# test_watch.net
KiCad netlist of a schematic drawn in Altium Designer
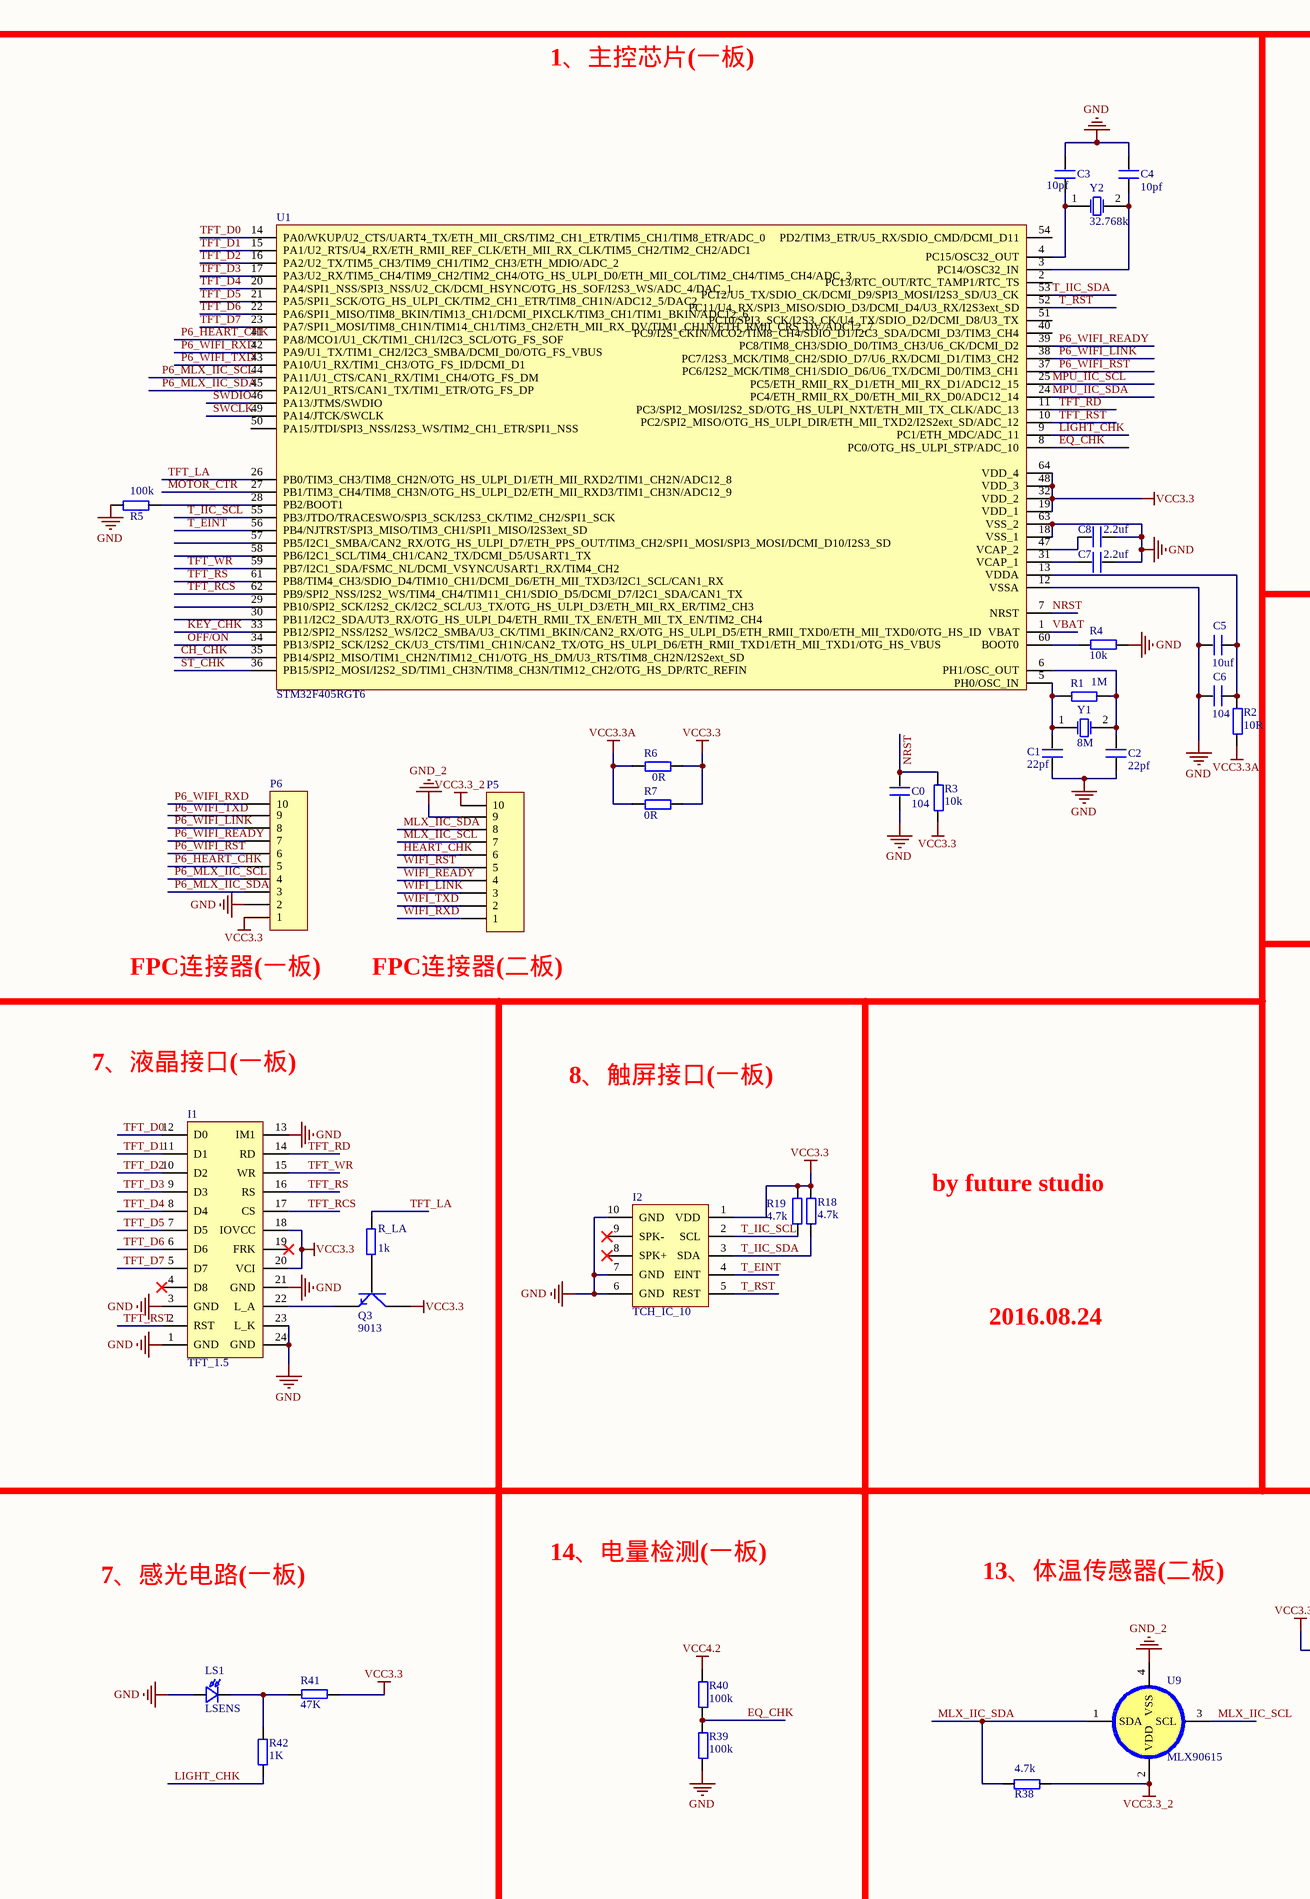
[diagram p0: test_watch.SchDoc, left]
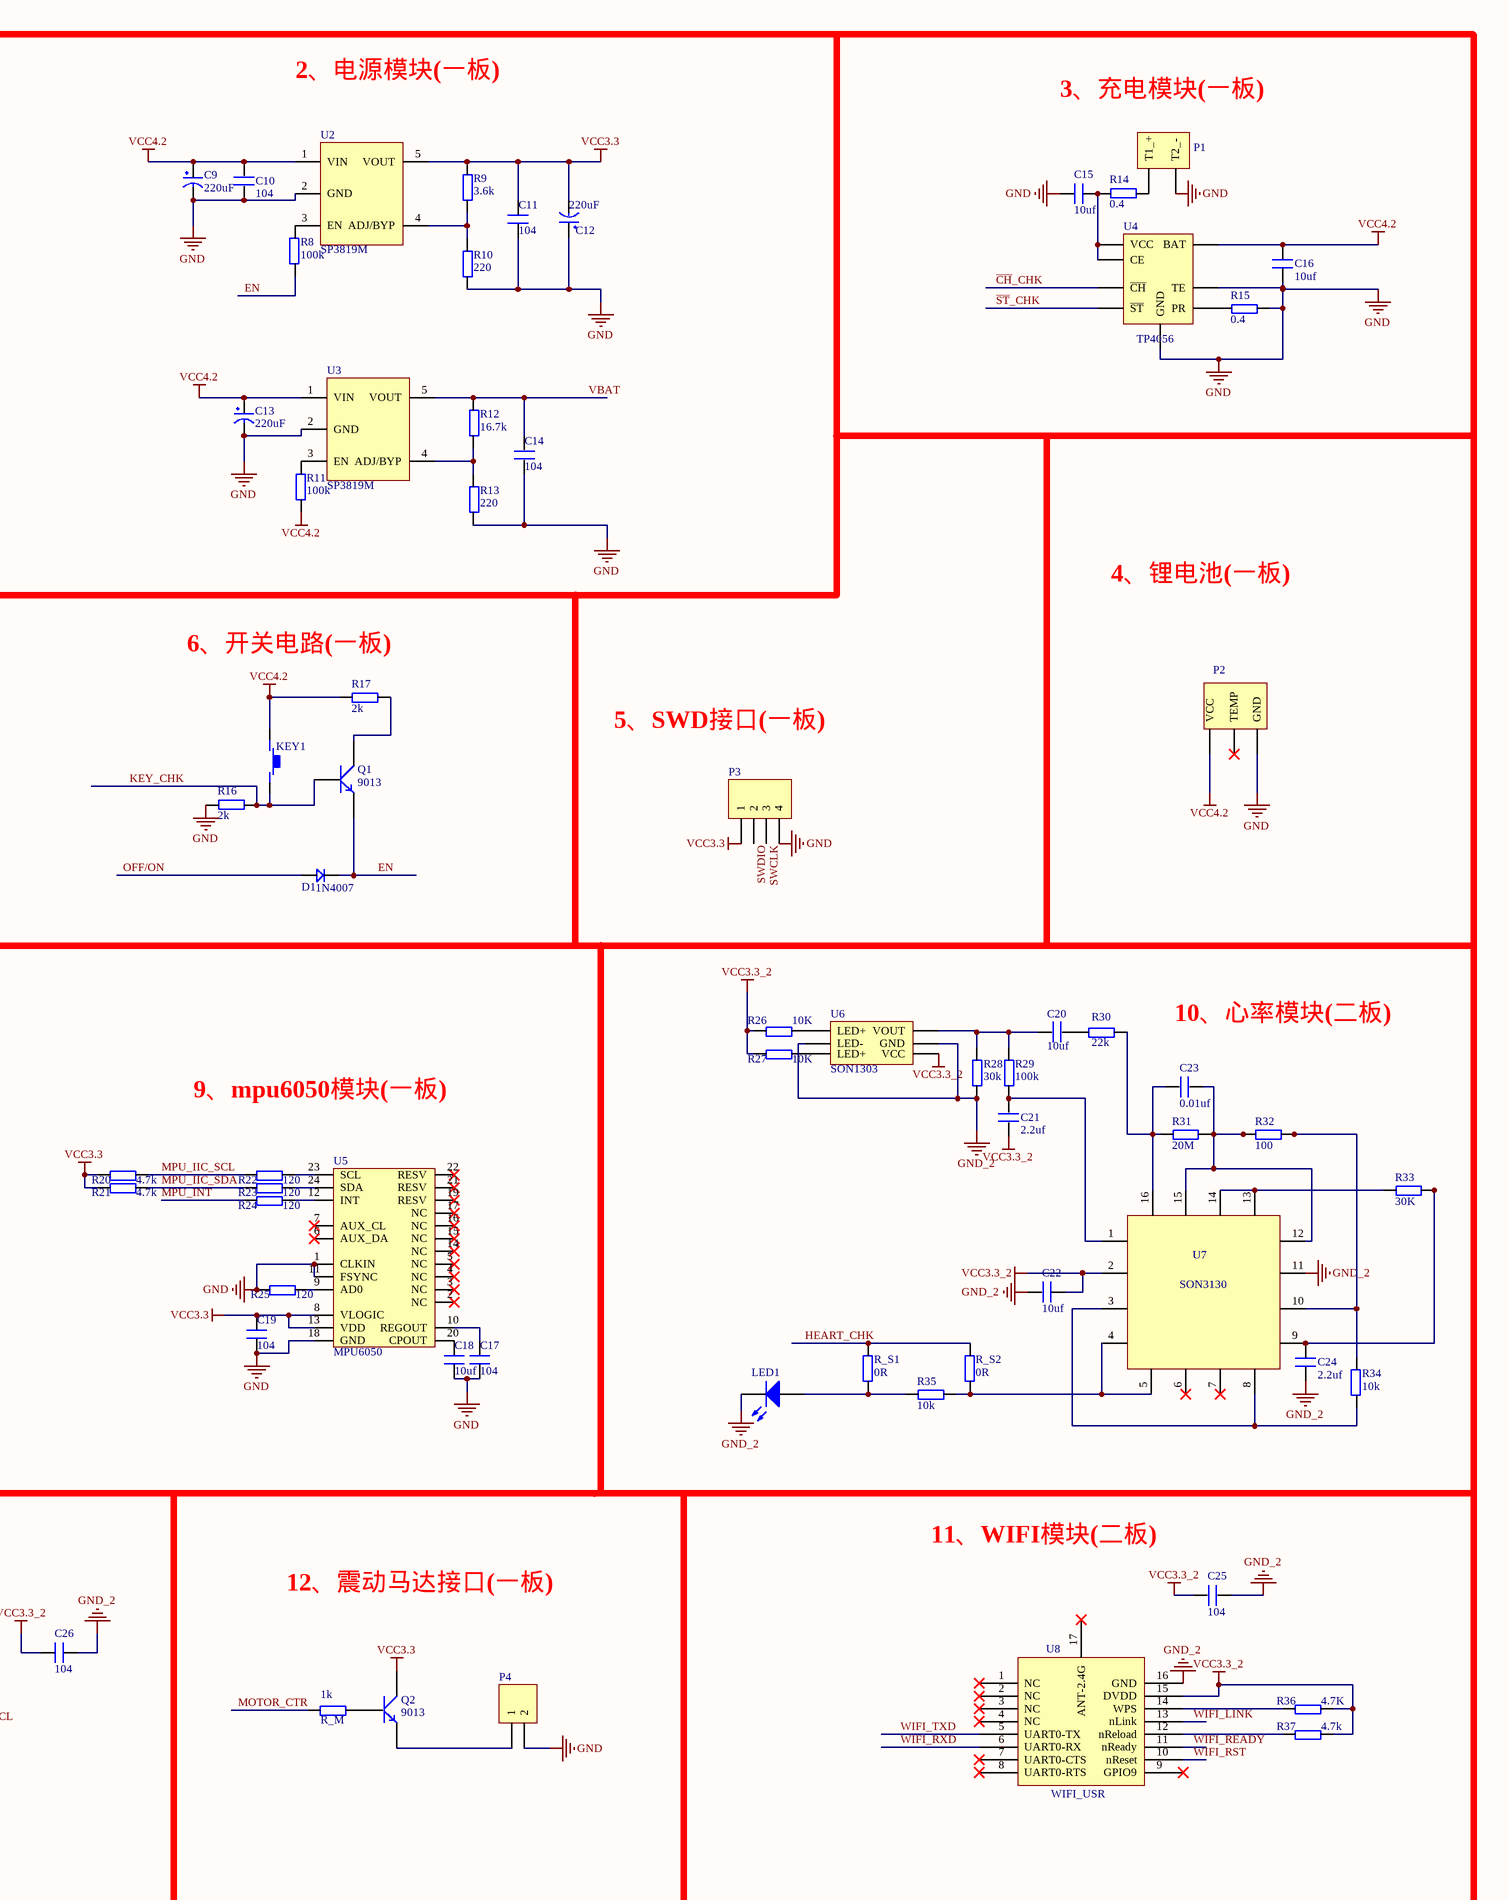
[diagram p1: test_watch.SchDoc, right]

(export (version "E")
  (design (tool "Eeschema 10.0.6"))
  (components
    (comp (ref "C0") (value "104") (footprint "C_0603") (libsource (lib "战舰STM32开发板底板封装库") (part "C")))
    (comp (ref "C1") (value "22pf") (footprint "C_0402") (libsource (lib "战舰STM32开发板底板封装库") (part "C")))
    (comp (ref "C2") (value "22pf") (footprint "C_0402") (libsource (lib "战舰STM32开发板底板封装库") (part "C")))
    (comp (ref "C3") (value "10pf") (footprint "C_0402") (libsource (lib "战舰STM32开发板底板封装库") (part "C")))
    (comp (ref "C4") (value "10pf") (footprint "C_0402") (libsource (lib "战舰STM32开发板底板封装库") (part "C")))
    (comp (ref "C5") (value "10uf") (footprint "C_0402") (libsource (lib "战舰STM32开发板底板封装库") (part "C")))
    (comp (ref "C6") (value "104") (footprint "C_0603") (libsource (lib "战舰STM32开发板底板封装库") (part "C")))
    (comp (ref "C7") (value "2.2uf") (footprint "C_0402") (libsource (lib "战舰STM32开发板底板封装库") (part "C")))
    (comp (ref "C8") (value "2.2uf") (footprint "C_0402") (libsource (lib "战舰STM32开发板底板封装库") (part "C")))
    (comp (ref "C9") (value "220uF") (footprint "C_3528") (libsource (lib "战舰STM32开发板底板封装库") (part "CAP")))
    (comp (ref "C10") (value "104") (footprint "C_0603") (libsource (lib "战舰STM32开发板底板封装库") (part "C")))
    (comp (ref "C11") (value "104") (footprint "C_0603") (libsource (lib "战舰STM32开发板底板封装库") (part "C")))
    (comp (ref "C12") (value "220uF") (footprint "C_3528") (libsource (lib "") (part "CAP_1")))
    (comp (ref "C13") (value "220uF") (footprint "C_3528") (libsource (lib "战舰STM32开发板底板封装库") (part "CAP")))
    (comp (ref "C14") (value "104") (footprint "C_0603") (libsource (lib "战舰STM32开发板底板封装库") (part "C")))
    (comp (ref "C15") (value "10uf") (footprint "C_0402") (libsource (lib "战舰STM32开发板底板封装库") (part "C")))
    (comp (ref "C16") (value "10uf") (footprint "C_0402") (libsource (lib "战舰STM32开发板底板封装库") (part "C")))
    (comp (ref "C17") (value "104") (footprint "C_0603") (libsource (lib "战舰STM32开发板底板封装库") (part "C")))
    (comp (ref "C18") (value "10uf") (footprint "C_0402") (libsource (lib "战舰STM32开发板底板封装库") (part "C")))
    (comp (ref "C19") (value "104") (footprint "C_0603") (libsource (lib "战舰STM32开发板底板封装库") (part "C")))
    (comp (ref "C20") (value "10uf") (footprint "C_0402") (libsource (lib "战舰STM32开发板底板封装库") (part "C")))
    (comp (ref "C21") (value "2.2uf") (footprint "C_0402") (libsource (lib "战舰STM32开发板底板封装库") (part "C")))
    (comp (ref "C22") (value "10uf") (footprint "C_0402") (libsource (lib "战舰STM32开发板底板封装库") (part "C")))
    (comp (ref "C23") (value "0.01uf") (footprint "C_0603") (libsource (lib "战舰STM32开发板底板封装库") (part "C")))
    (comp (ref "C24") (value "2.2uf") (footprint "C_0402") (libsource (lib "战舰STM32开发板底板封装库") (part "C")))
    (comp (ref "C25") (value "104") (footprint "C_0603") (libsource (lib "战舰STM32开发板底板封装库") (part "C")))
    (comp (ref "C26") (value "104") (footprint "C_0603") (libsource (lib "战舰STM32开发板底板封装库") (part "C")))
    (comp (ref "D1") (value "1N4007") (footprint "D_0805") (libsource (lib "战舰STM32开发板底板封装库") (part "D")))
    (comp (ref "I1")
      (value "TFT_1.5")
      (footprint "DF37NB-24DS-0.4V - duplicate")
      (libsource (lib "test_1") (part "TFT_1.5"))
    )
    (comp (ref "I2")
      (value "TCH_IC_10")
      (footprint "DF37NB-10DS-0.4V")
      (libsource (lib "test_1") (part "TCH_IC_10"))
    )
    (comp (ref "KEY1") (value "button_2pin") (footprint "SMD2_3.5") (libsource (lib "test_1") (part "KEY_2")))
    (comp (ref "LED1")
      (value "LED1")
      (footprint "D_0603")
      (description "Typical RED, GREEN, YELLOW, AMBER GaAs LED")
      (fields (field (name "PUBLISHER") "Altium Limited"))
      (libsource (lib "战舰STM32开发板底板封装库") (part "LED2"))
    )
    (comp (ref "LS1")
      (value "LSENS")
      (footprint "0805")
      (description "光敏电阻")
      (libsource (lib "test_1") (part "光敏电阻"))
    )
    (comp (ref "P1")
      (value "contactor")
      (footprint "CHARGE_2")
      (description "充电触点")
      (libsource (lib "test_1") (part "contactor"))
    )
    (comp (ref "P2")
      (value "CELL")
      (footprint "CELL_2")
      (description "锂电池")
      (libsource (lib "test_1") (part "CELL"))
    )
    (comp (ref "P3")
      (value "Header 4")
      (footprint "SWD")
      (description "Header, 4-Pin")
      (fields (field (name "PUBLISHER") "Altium Limited"))
      (libsource (lib "战舰STM32开发板底板封装库") (part "Header 4"))
    )
    (comp (ref "P4")
      (value "MIC/LINE")
      (footprint "CHARGE_2")
      (description "Header, 2-Pin")
      (fields (field (name "PUBLISHER") "Altium Limited"))
      (libsource (lib "战舰STM32开发板底板封装库") (part "Header 2_1"))
    )
    (comp (ref "P5")
      (value "Header-10")
      (footprint "FPC_10_0.5")
      (libsource (lib "test_1") (part "Header-10"))
    )
    (comp (ref "P6")
      (value "Header-10")
      (footprint "FPC_10_0.5")
      (libsource (lib "test_1") (part "Header-10"))
    )
    (comp (ref "Q1") (value "9013") (footprint "SOT-23R") (libsource (lib "test_1") (part "NPN")))
    (comp (ref "Q2") (value "9013") (footprint "SOT-23R") (libsource (lib "test_1") (part "NPN")))
    (comp (ref "Q3") (value "9013") (footprint "SOT-23R") (libsource (lib "test_1") (part "NPN")))
    (comp (ref "R1") (value "1M") (footprint "R_0402") (libsource (lib "战舰STM32开发板底板封装库") (part "R")))
    (comp (ref "R2") (value "10R") (footprint "R_0402") (libsource (lib "战舰STM32开发板底板封装库") (part "R")))
    (comp (ref "R3") (value "10k") (footprint "R_0402") (libsource (lib "战舰STM32开发板底板封装库") (part "R")))
    (comp (ref "R4") (value "10k") (footprint "R_0402") (libsource (lib "战舰STM32开发板底板封装库") (part "R")))
    (comp (ref "R5") (value "100k") (footprint "R_0402") (libsource (lib "战舰STM32开发板底板封装库") (part "R")))
    (comp (ref "R6") (value "0R") (footprint "R_0402") (libsource (lib "战舰STM32开发板底板封装库") (part "R")))
    (comp (ref "R7") (value "0R") (footprint "R_0402") (libsource (lib "战舰STM32开发板底板封装库") (part "R")))
    (comp (ref "R8") (value "100k") (footprint "R_0402") (libsource (lib "战舰STM32开发板底板封装库") (part "R")))
    (comp (ref "R9") (value "3.6k") (footprint "R_0603") (libsource (lib "战舰STM32开发板底板封装库") (part "R")))
    (comp (ref "R10") (value "220") (footprint "R_0402") (libsource (lib "战舰STM32开发板底板封装库") (part "R")))
    (comp (ref "R11") (value "100k") (footprint "R_0402") (libsource (lib "战舰STM32开发板底板封装库") (part "R")))
    (comp (ref "R12") (value "16.7k") (footprint "R_0603") (libsource (lib "战舰STM32开发板底板封装库") (part "R")))
    (comp (ref "R13") (value "220") (footprint "R_0402") (libsource (lib "战舰STM32开发板底板封装库") (part "R")))
    (comp (ref "R14") (value "0.4") (footprint "R_1206") (libsource (lib "战舰STM32开发板底板封装库") (part "R")))
    (comp (ref "R15") (value "0.4") (footprint "R_1206") (libsource (lib "战舰STM32开发板底板封装库") (part "R")))
    (comp (ref "R16") (value "2k") (footprint "R_0402") (libsource (lib "战舰STM32开发板底板封装库") (part "R")))
    (comp (ref "R17") (value "2k") (footprint "R_0402") (libsource (lib "战舰STM32开发板底板封装库") (part "R")))
    (comp (ref "R18") (value "4.7k") (footprint "R_0402") (libsource (lib "战舰STM32开发板底板封装库") (part "R")))
    (comp (ref "R19") (value "4.7k") (footprint "R_0402") (libsource (lib "战舰STM32开发板底板封装库") (part "R")))
    (comp (ref "R20") (value "4.7k") (footprint "R_0402") (libsource (lib "战舰STM32开发板底板封装库") (part "R")))
    (comp (ref "R21") (value "4.7k") (footprint "R_0402") (libsource (lib "战舰STM32开发板底板封装库") (part "R")))
    (comp (ref "R22") (value "120") (footprint "R_0402") (libsource (lib "战舰STM32开发板底板封装库") (part "R")))
    (comp (ref "R23") (value "120") (footprint "R_0402") (libsource (lib "战舰STM32开发板底板封装库") (part "R")))
    (comp (ref "R24") (value "120") (footprint "R_0402") (libsource (lib "战舰STM32开发板底板封装库") (part "R")))
    (comp (ref "R25") (value "120") (footprint "R_0402") (libsource (lib "战舰STM32开发板底板封装库") (part "R")))
    (comp (ref "R26") (value "10K") (footprint "R_0402") (libsource (lib "战舰STM32开发板底板封装库") (part "R")))
    (comp (ref "R27") (value "10K") (footprint "R_0402") (libsource (lib "战舰STM32开发板底板封装库") (part "R")))
    (comp (ref "R28") (value "30k") (footprint "R_0402") (libsource (lib "战舰STM32开发板底板封装库") (part "R")))
    (comp (ref "R29") (value "100k") (footprint "R_0402") (libsource (lib "战舰STM32开发板底板封装库") (part "R")))
    (comp (ref "R30") (value "22k") (footprint "R_0402") (libsource (lib "战舰STM32开发板底板封装库") (part "R")))
    (comp (ref "R31") (value "20M") (footprint "R_0603") (libsource (lib "战舰STM32开发板底板封装库") (part "R")))
    (comp (ref "R32") (value "100") (footprint "R_0402") (libsource (lib "战舰STM32开发板底板封装库") (part "R")))
    (comp (ref "R33") (value "30K") (footprint "R_0402") (libsource (lib "战舰STM32开发板底板封装库") (part "R")))
    (comp (ref "R34") (value "10k") (footprint "R_0402") (libsource (lib "战舰STM32开发板底板封装库") (part "R")))
    (comp (ref "R35") (value "10k") (footprint "R_0402") (libsource (lib "战舰STM32开发板底板封装库") (part "R")))
    (comp (ref "R36") (value "4.7K") (footprint "R_0402") (libsource (lib "战舰STM32开发板底板封装库") (part "R")))
    (comp (ref "R37") (value "4.7k") (footprint "R_0402") (libsource (lib "战舰STM32开发板底板封装库") (part "R")))
    (comp (ref "R38") (value "4.7k") (footprint "R_0402") (libsource (lib "战舰STM32开发板底板封装库") (part "R")))
    (comp (ref "R39") (value "100k") (footprint "R_0402") (libsource (lib "战舰STM32开发板底板封装库") (part "R")))
    (comp (ref "R40") (value "100k") (footprint "R_0402") (libsource (lib "战舰STM32开发板底板封装库") (part "R")))
    (comp (ref "R41") (value "47K") (footprint "R_0402") (libsource (lib "战舰STM32开发板底板封装库") (part "R")))
    (comp (ref "R42") (value "1K") (footprint "R_0402") (libsource (lib "战舰STM32开发板底板封装库") (part "R")))
    (comp (ref "R_LA") (value "1k") (footprint "R_0402") (libsource (lib "战舰STM32开发板底板封装库") (part "R")))
    (comp (ref "R_M") (value "1k") (footprint "R_0402") (libsource (lib "战舰STM32开发板底板封装库") (part "R")))
    (comp (ref "R_S1") (value "0R") (footprint "R_0402") (libsource (lib "战舰STM32开发板底板封装库") (part "R")))
    (comp (ref "R_S2") (value "0R") (footprint "R_0402") (libsource (lib "战舰STM32开发板底板封装库") (part "R")))
    (comp (ref "U1")
      (value "STM32F405RGT6")
      (footprint "LQFP64")
      (description "F405_64脚")
      (libsource (lib "STM32F407VET6mini最小系统-原理图库") (part "STM32F405RGT6"))
    )
    (comp (ref "U2")
      (value "SP3819M")
      (footprint "SPX3819")
      (description "稳压器")
      (libsource (lib "test_1") (part "SP3819M"))
    )
    (comp (ref "U3")
      (value "SP3819M")
      (footprint "SPX3819")
      (description "稳压器")
      (libsource (lib "test_1") (part "SP3819M"))
    )
    (comp (ref "U4")
      (value "TP4056")
      (footprint "TP4056")
      (description "充电芯片")
      (libsource (lib "test_1") (part "TP4056"))
    )
    (comp (ref "U5")
      (value "MPU6050")
      (footprint "MPU6050_QFN24")
      (description "9轴运动处理传感器")
      (libsource (lib "ATK-MPU6050六轴传感器模块") (part "MPU6050"))
    )
    (comp (ref "U6")
      (value "SON1303")
      (footprint "SON7015")
      (description "心率传感器")
      (libsource (lib "test_1") (part "SON1303"))
    )
    (comp (ref "U7")
      (value "SON3130")
      (footprint "SON3130_QFN16")
      (description "心率传感器")
      (libsource (lib "test_1") (part "SON3130"))
    )
    (comp (ref "U8")
      (value "WIFI_USR")
      (footprint "WIFI_USR")
      (description "wifi模块")
      (libsource (lib "test_1") (part "WIFI_USR"))
    )
    (comp (ref "U9")
      (value "MLX90615")
      (footprint "MLX90615")
      (description "体温传感器")
      (libsource (lib "test_1") (part "MLX90615"))
    )
    (comp (ref "Y1")
      (value "8M")
      (footprint "TXAL_5032_2")
      (description "32.768k")
      (libsource (lib "test_1") (part "XTAL_1"))
    )
    (comp (ref "Y2") (value "32.768k") (footprint "TXAL_3215") (libsource (lib "test_1") (part "XTAL_1")))
  )
  (nets
    (net (code "1") (name "/EN") (class "Default")
      (node (ref "D1") (pin "2") (pintype "passive"))
      (node (ref "Q1") (pin "2") (pinfunction "E_2") (pintype "passive"))
      (node (ref "R8") (pin "2") (pintype "passive"))
    )
    (net (code "2") (name "/EQ_CHK") (class "Default")
      (node (ref "R39") (pin "2") (pintype "passive"))
      (node (ref "R40") (pin "1") (pintype "passive"))
      (node (ref "U1") (pin "8") (pinfunction "PC0/OTG_HS_ULPI_STP/ADC_10_8") (pintype "passive"))
    )
    (net (code "3") (name "/HEART_CHK") (class "Default")
      (node (ref "P5") (pin "6") (pinfunction "6_6") (pintype "passive"))
      (node (ref "R_S1") (pin "1") (pintype "passive"))
      (node (ref "R_S2") (pin "1") (pintype "passive"))
    )
    (net (code "4") (name "/KEY_CHK") (class "Default")
      (node (ref "KEY1") (pin "2") (pinfunction "P2_2") (pintype "passive"))
      (node (ref "Q1") (pin "1") (pinfunction "B_1") (pintype "passive"))
      (node (ref "R16") (pin "1") (pintype "passive"))
      (node (ref "U1") (pin "33") (pinfunction "PB12/SPI2_NSS/I2S2_WS/I2C2_SMBA/U3_CK/TIM1_BKIN/CAN2_RX/OTG_HS_ULPI_D5/ETH_RMII_TXD0/ETH_MII_TXD0/OTG_HS_ID_33") (pintype "passive"))
    )
    (net (code "5") (name "/LIGHT_CHK") (class "Default")
      (node (ref "R42") (pin "2") (pintype "passive"))
      (node (ref "U1") (pin "9") (pinfunction "PC1/ETH_MDC/ADC_11_9") (pintype "passive"))
    )
    (net (code "6") (name "/MLX_IIC_SCL") (class "Default")
      (node (ref "P5") (pin "7") (pinfunction "7_7") (pintype "passive"))
      (node (ref "U9") (pin "3") (pinfunction "SCL_3") (pintype "passive"))
    )
    (net (code "7") (name "/MLX_IIC_SDA") (class "Default")
      (node (ref "P5") (pin "8") (pinfunction "8_8") (pintype "passive"))
      (node (ref "R38") (pin "1") (pintype "passive"))
      (node (ref "U9") (pin "1") (pinfunction "SDA_1") (pintype "passive"))
    )
    (net (code "8") (name "/MOTOR_CTR") (class "Default")
      (node (ref "R_M") (pin "1") (pintype "passive"))
      (node (ref "U1") (pin "27") (pinfunction "PB1/TIM3_CH4/TIM8_CH3N/OTG_HS_ULPI_D2/ETH_MII_RXD3/TIM1_CH3N/ADC12_9_27") (pintype "passive"))
    )
    (net (code "9") (name "/MPU_IIC_SCL") (class "Default")
      (node (ref "R20") (pin "2") (pintype "passive"))
      (node (ref "R22") (pin "1") (pintype "passive"))
      (node (ref "U1") (pin "25") (pinfunction "PC5/ETH_RMII_RX_D1/ETH_MII_RX_D1/ADC12_15_25") (pintype "passive"))
    )
    (net (code "10") (name "/MPU_IIC_SDA") (class "Default")
      (node (ref "R21") (pin "2") (pintype "passive"))
      (node (ref "R23") (pin "1") (pintype "passive"))
      (node (ref "U1") (pin "24") (pinfunction "PC4/ETH_RMII_RX_D0/ETH_MII_RX_D0/ADC12_14_24") (pintype "passive"))
    )
    (net (code "11") (name "/MPU_INT") (class "Default") (node (ref "R24") (pin "1") (pintype "passive")))
    (net (code "12") (name "/NRST") (class "Default")
      (node (ref "C0") (pin "1") (pintype "passive"))
      (node (ref "R3") (pin "2") (pintype "passive"))
      (node (ref "U1") (pin "7") (pinfunction "NRST_7") (pintype "passive"))
    )
    (net (code "13") (name "/OFF{slash}ON") (class "Default")
      (node (ref "D1") (pin "1") (pintype "passive"))
      (node (ref "U1") (pin "34") (pinfunction "PB13/SPI2_SCK/I2S2_CK/U3_CTS/TIM1_CH1N/CAN2_TX/OTG_HS_ULPI_D6/ETH_RMII_TXD1/ETH_MII_TXD1/OTG_HS_VBUS_34") (pintype "passive"))
    )
    (net (code "14") (name "/P6_HEART_CHK") (class "Default")
      (node (ref "P6") (pin "5") (pinfunction "5_5") (pintype "passive"))
      (node (ref "U1") (pin "41") (pinfunction "PA8/MCO1/U1_CK/TIM1_CH1/I2C3_SCL/OTG_FS_SOF_41") (pintype "passive"))
    )
    (net (code "15") (name "/P6_MLX_IIC_SCL") (class "Default")
      (node (ref "P6") (pin "4") (pinfunction "4_4") (pintype "passive"))
      (node (ref "U1") (pin "44") (pinfunction "PA11/U1_CTS/CAN1_RX/TIM1_CH4/OTG_FS_DM_44") (pintype "passive"))
    )
    (net (code "16") (name "/P6_MLX_IIC_SDA") (class "Default")
      (node (ref "P6") (pin "3") (pinfunction "3_3") (pintype "passive"))
      (node (ref "U1") (pin "45") (pinfunction "PA12/U1_RTS/CAN1_TX/TIM1_ETR/OTG_FS_DP_45") (pintype "passive"))
    )
    (net (code "17") (name "/P6_WIFI_LINK") (class "Default")
      (node (ref "P6") (pin "8") (pinfunction "8_8") (pintype "passive"))
      (node (ref "U1") (pin "38") (pinfunction "PC7/I2S3_MCK/TIM8_CH2/SDIO_D7/U6_RX/DCMI_D1/TIM3_CH2_38") (pintype "passive"))
    )
    (net (code "18") (name "/P6_WIFI_READY") (class "Default")
      (node (ref "P6") (pin "7") (pinfunction "7_7") (pintype "passive"))
      (node (ref "U1") (pin "39") (pinfunction "PC8/TIM8_CH3/SDIO_D0/TIM3_CH3/U6_CK/DCMI_D2_39") (pintype "passive"))
    )
    (net (code "19") (name "/P6_WIFI_RST") (class "Default")
      (node (ref "P6") (pin "6") (pinfunction "6_6") (pintype "passive"))
      (node (ref "U1") (pin "37") (pinfunction "PC6/I2S2_MCK/TIM8_CH1/SDIO_D6/U6_TX/DCMI_D0/TIM3_CH1_37") (pintype "passive"))
    )
    (net (code "20") (name "/P6_WIFI_RXD") (class "Default")
      (node (ref "P6") (pin "10") (pinfunction "10_10") (pintype "passive"))
      (node (ref "U1") (pin "42") (pinfunction "PA9/U1_TX/TIM1_CH2/I2C3_SMBA/DCMI_D0/OTG_FS_VBUS_42") (pintype "passive"))
    )
    (net (code "21") (name "/P6_WIFI_TXD") (class "Default")
      (node (ref "P6") (pin "9") (pinfunction "9_9") (pintype "passive"))
      (node (ref "U1") (pin "43") (pinfunction "PA10/U1_RX/TIM1_CH3/OTG_FS_ID/DCMI_D1_43") (pintype "passive"))
    )
    (net (code "22") (name "/SWCLK") (class "Default")
      (node (ref "P3") (pin "3") (pinfunction "3_3") (pintype "passive"))
      (node (ref "U1") (pin "49") (pinfunction "PA14/JTCK/SWCLK_49") (pintype "passive"))
    )
    (net (code "23") (name "/SWDIO") (class "Default")
      (node (ref "P3") (pin "2") (pinfunction "2_2") (pintype "passive"))
      (node (ref "U1") (pin "46") (pinfunction "PA13/JTMS/SWDIO_46") (pintype "passive"))
    )
    (net (code "24") (name "/TFT_D0") (class "Default")
      (node (ref "I1") (pin "12") (pinfunction "D0_12") (pintype "power_in"))
      (node (ref "U1") (pin "14") (pinfunction "PA0/WKUP/U2_CTS/UART4_TX/ETH_MII_CRS/TIM2_CH1_ETR/TIM5_CH1/TIM8_ETR/ADC_0_14") (pintype "passive"))
    )
    (net (code "25") (name "/TFT_D1") (class "Default")
      (node (ref "I1") (pin "11") (pinfunction "D1_11") (pintype "power_in"))
      (node (ref "U1") (pin "15") (pinfunction "PA1/U2_RTS/U4_RX/ETH_RMII_REF_CLK/ETH_MII_RX_CLK/TIM5_CH2/TIM2_CH2/ADC1_15") (pintype "passive"))
    )
    (net (code "26") (name "/TFT_D2") (class "Default")
      (node (ref "I1") (pin "10") (pinfunction "D2_10") (pintype "power_in"))
      (node (ref "U1") (pin "16") (pinfunction "PA2/U2_TX/TIM5_CH3/TIM9_CH1/TIM2_CH3/ETH_MDIO/ADC_2_16") (pintype "passive"))
    )
    (net (code "27") (name "/TFT_D3") (class "Default")
      (node (ref "I1") (pin "9") (pinfunction "D3_9") (pintype "power_in"))
      (node (ref "U1") (pin "17") (pinfunction "PA3/U2_RX/TIM5_CH4/TIM9_CH2/TIM2_CH4/OTG_HS_ULPI_D0/ETH_MII_COL/TIM2_CH4/TIM5_CH4/ADC_3_17") (pintype "passive"))
    )
    (net (code "28") (name "/TFT_D4") (class "Default")
      (node (ref "I1") (pin "8") (pinfunction "D4_8") (pintype "power_in"))
      (node (ref "U1") (pin "20") (pinfunction "PA4/SPI1_NSS/SPI3_NSS/U2_CK/DCMI_HSYNC/OTG_HS_SOF/I2S3_WS/ADC_4/DAC_1_20") (pintype "passive"))
    )
    (net (code "29") (name "/TFT_D5") (class "Default")
      (node (ref "I1") (pin "7") (pinfunction "D5_7") (pintype "power_in"))
      (node (ref "U1") (pin "21") (pinfunction "PA5/SPI1_SCK/OTG_HS_ULPI_CK/TIM2_CH1_ETR/TIM8_CH1N/ADC12_5/DAC2_21") (pintype "passive"))
    )
    (net (code "30") (name "/TFT_D6") (class "Default")
      (node (ref "I1") (pin "6") (pinfunction "D6_6") (pintype "power_in"))
      (node (ref "U1") (pin "22") (pinfunction "PA6/SPI1_MISO/TIM8_BKIN/TIM13_CH1/DCMI_PIXCLK/TIM3_CH1/TIM1_BKIN/ADC12_6_22") (pintype "passive"))
    )
    (net (code "31") (name "/TFT_D7") (class "Default")
      (node (ref "I1") (pin "5") (pinfunction "D7_5") (pintype "power_in"))
      (node (ref "U1") (pin "23") (pinfunction "PA7/SPI1_MOSI/TIM8_CH1N/TIM14_CH1/TIM3_CH2/ETH_MII_RX_DV/TIM1_CH1N/ETH_RMII_CRS_DV/ADC12_7_23") (pintype "passive"))
    )
    (net (code "32") (name "/TFT_LA") (class "Default")
      (node (ref "R_LA") (pin "1") (pintype "passive"))
      (node (ref "U1") (pin "26") (pinfunction "PB0/TIM3_CH3/TIM8_CH2N/OTG_HS_ULPI_D1/ETH_MII_RXD2/TIM1_CH2N/ADC12_8_26") (pintype "passive"))
    )
    (net (code "33") (name "/TFT_RCS") (class "Default")
      (node (ref "I1") (pin "17") (pinfunction "CS_17") (pintype "power_in"))
      (node (ref "U1") (pin "62") (pinfunction "PB9/SPI2_NSS/I2S2_WS/TIM4_CH4/TIM11_CH1/SDIO_D5/DCMI_D7/I2C1_SDA/CAN1_TX_62") (pintype "passive"))
    )
    (net (code "34") (name "/TFT_RD") (class "Default")
      (node (ref "I1") (pin "14") (pinfunction "RD_14") (pintype "power_in"))
      (node (ref "U1") (pin "11") (pinfunction "PC3/SPI2_MOSI/I2S2_SD/OTG_HS_ULPI_NXT/ETH_MII_TX_CLK/ADC_13_11") (pintype "passive"))
    )
    (net (code "35") (name "/TFT_RS") (class "Default")
      (node (ref "I1") (pin "16") (pinfunction "RS_16") (pintype "power_in"))
      (node (ref "U1") (pin "61") (pinfunction "PB8/TIM4_CH3/SDIO_D4/TIM10_CH1/DCMI_D6/ETH_MII_TXD3/I2C1_SCL/CAN1_RX_61") (pintype "passive"))
    )
    (net (code "36") (name "/TFT_RST") (class "Default")
      (node (ref "I1") (pin "2") (pinfunction "RST_2") (pintype "power_in"))
      (node (ref "U1") (pin "10") (pinfunction "PC2/SPI2_MISO/OTG_HS_ULPI_DIR/ETH_MII_TXD2/I2S2ext_SD/ADC_12_10") (pintype "passive"))
    )
    (net (code "37") (name "/TFT_WR") (class "Default")
      (node (ref "I1") (pin "15") (pinfunction "WR_15") (pintype "power_in"))
      (node (ref "U1") (pin "59") (pinfunction "PB7/I2C1_SDA/FSMC_NL/DCMI_VSYNC/USART1_RX/TIM4_CH2_59") (pintype "passive"))
    )
    (net (code "38") (name "/T_EINT") (class "Default")
      (node (ref "I2") (pin "4") (pinfunction "EINT_4") (pintype "power_in"))
      (node (ref "U1") (pin "56") (pinfunction "PB4/NJTRST/SPI3_MISO/TIM3_CH1/SPI1_MISO/I2S3ext_SD_56") (pintype "passive"))
    )
    (net (code "39") (name "/T_IIC_SCL") (class "Default")
      (node (ref "I2") (pin "2") (pinfunction "SCL_2") (pintype "power_in"))
      (node (ref "R19") (pin "2") (pintype "passive"))
      (node (ref "U1") (pin "55") (pinfunction "PB3/JTDO/TRACESWO/SPI3_SCK/I2S3_CK/TIM2_CH2/SPI1_SCK_55") (pintype "passive"))
    )
    (net (code "40") (name "/T_IIC_SDA") (class "Default")
      (node (ref "I2") (pin "3") (pinfunction "SDA_3") (pintype "power_in"))
      (node (ref "R18") (pin "1") (pintype "passive"))
      (node (ref "U1") (pin "53") (pinfunction "PC12/U5_TX/SDIO_CK/DCMI_D9/SPI3_MOSI/I2S3_SD/U3_CK_53") (pintype "passive"))
    )
    (net (code "41") (name "/T_RST") (class "Default")
      (node (ref "I2") (pin "5") (pinfunction "REST_5") (pintype "power_in"))
      (node (ref "U1") (pin "52") (pinfunction "PC11/U4_RX/SPI3_MISO/SDIO_D3/DCMI_D4/U3_RX/I2S3ext_SD_52") (pintype "passive"))
    )
    (net (code "42") (name "/VBAT") (class "Default")
      (node (ref "C14") (pin "1") (pintype "passive"))
      (node (ref "R12") (pin "2") (pintype "passive"))
      (node (ref "U1") (pin "1") (pinfunction "VBAT_1") (pintype "passive"))
      (node (ref "U3") (pin "5") (pinfunction "VOUT_5") (pintype "passive"))
    )
    (net (code "43") (name "/WIFI_LINK") (class "Default")
      (node (ref "P5") (pin "3") (pinfunction "3_3") (pintype "passive"))
      (node (ref "U8") (pin "13") (pinfunction "nLink_13") (pintype "passive"))
    )
    (net (code "44") (name "/WIFI_READY") (class "Default")
      (node (ref "P5") (pin "4") (pinfunction "4_4") (pintype "passive"))
      (node (ref "U8") (pin "11") (pinfunction "nReady_11") (pintype "passive"))
    )
    (net (code "45") (name "/WIFI_RST") (class "Default")
      (node (ref "P5") (pin "5") (pinfunction "5_5") (pintype "passive"))
      (node (ref "U8") (pin "10") (pinfunction "nReset_10") (pintype "passive"))
    )
    (net (code "46") (name "/WIFI_RXD") (class "Default")
      (node (ref "P5") (pin "1") (pinfunction "1_1") (pintype "passive"))
      (node (ref "U8") (pin "6") (pinfunction "UART0-RX_6") (pintype "passive"))
    )
    (net (code "47") (name "/WIFI_TXD") (class "Default")
      (node (ref "P5") (pin "2") (pinfunction "2_2") (pintype "passive"))
      (node (ref "U8") (pin "5") (pinfunction "UART0-TX_5") (pintype "passive"))
    )
    (net (code "48") (name "/~{CH}_CHK") (class "Default")
      (node (ref "U1") (pin "35") (pinfunction "PB14/SPI2_MISO/TIM1_CH2N/TIM12_CH1/OTG_HS_DM/U3_RTS/TIM8_CH2N/I2S2ext_SD_35") (pintype "passive"))
      (node (ref "U4") (pin "7") (pinfunction "~{CH}_7") (pintype "passive"))
    )
    (net (code "49") (name "/~{ST}_CHK") (class "Default")
      (node (ref "U1") (pin "36") (pinfunction "PB15/SPI2_MOSI/I2S2_SD/TIM1_CH3N/TIM8_CH3N/TIM12_CH2/OTG_HS_DP/RTC_REFIN_36") (pintype "passive"))
      (node (ref "U4") (pin "6") (pinfunction "~{ST}_6") (pintype "passive"))
    )
    (net (code "50") (name "GND") (class "Default")
      (node (ref "C0") (pin "2") (pintype "passive"))
      (node (ref "C1") (pin "1") (pintype "passive"))
      (node (ref "C10") (pin "2") (pintype "passive"))
      (node (ref "C11") (pin "2") (pintype "passive"))
      (node (ref "C12") (pin "1") (pinfunction "VCC_1") (pintype "passive"))
      (node (ref "C13") (pin "2") (pinfunction "GND_2") (pintype "passive"))
      (node (ref "C14") (pin "2") (pintype "passive"))
      (node (ref "C15") (pin "2") (pintype "passive"))
      (node (ref "C16") (pin "1") (pintype "passive"))
      (node (ref "C17") (pin "1") (pintype "passive"))
      (node (ref "C18") (pin "1") (pintype "passive"))
      (node (ref "C19") (pin "1") (pintype "passive"))
      (node (ref "C2") (pin "1") (pintype "passive"))
      (node (ref "C3") (pin "2") (pintype "passive"))
      (node (ref "C4") (pin "2") (pintype "passive"))
      (node (ref "C5") (pin "2") (pintype "passive"))
      (node (ref "C6") (pin "2") (pintype "passive"))
      (node (ref "C7") (pin "2") (pintype "passive"))
      (node (ref "C8") (pin "2") (pintype "passive"))
      (node (ref "C9") (pin "2") (pinfunction "GND_2") (pintype "passive"))
      (node (ref "I1") (pin "1") (pinfunction "GND_1") (pintype "power_in"))
      (node (ref "I1") (pin "13") (pinfunction "IM1_13") (pintype "power_in"))
      (node (ref "I1") (pin "21") (pinfunction "GND_21") (pintype "power_in"))
      (node (ref "I1") (pin "23") (pinfunction "L_K_23") (pintype "power_in"))
      (node (ref "I1") (pin "24") (pinfunction "GND_24") (pintype "power_in"))
      (node (ref "I1") (pin "3") (pinfunction "GND_3") (pintype "power_in"))
      (node (ref "I2") (pin "10") (pinfunction "GND_10") (pintype "power_in"))
      (node (ref "I2") (pin "6") (pinfunction "GND_6") (pintype "power_in"))
      (node (ref "I2") (pin "7") (pinfunction "GND_7") (pintype "power_in"))
      (node (ref "LS1") (pin "1") (pinfunction "1_1") (pintype "passive"))
      (node (ref "P1") (pin "2") (pinfunction "T2_-_2") (pintype "passive"))
      (node (ref "P2") (pin "2") (pinfunction "GND_2") (pintype "passive"))
      (node (ref "P3") (pin "4") (pinfunction "4_4") (pintype "passive"))
      (node (ref "P4") (pin "2") (pinfunction "2_2") (pintype "passive"))
      (node (ref "P6") (pin "2") (pinfunction "2_2") (pintype "passive"))
      (node (ref "R10") (pin "1") (pintype "passive"))
      (node (ref "R13") (pin "1") (pintype "passive"))
      (node (ref "R15") (pin "2") (pintype "passive"))
      (node (ref "R16") (pin "2") (pintype "passive"))
      (node (ref "R25") (pin "1") (pintype "passive"))
      (node (ref "R39") (pin "1") (pintype "passive"))
      (node (ref "R4") (pin "1") (pintype "passive"))
      (node (ref "R5") (pin "1") (pintype "passive"))
      (node (ref "U1") (pin "12") (pinfunction "VSSA_12") (pintype "passive"))
      (node (ref "U1") (pin "18") (pinfunction "VSS_1_18") (pintype "passive"))
      (node (ref "U1") (pin "63") (pinfunction "VSS_2_63") (pintype "passive"))
      (node (ref "U2") (pin "2") (pinfunction "GND_2") (pintype "passive"))
      (node (ref "U3") (pin "2") (pinfunction "GND_2") (pintype "passive"))
      (node (ref "U4") (pin "1") (pinfunction "TE_1") (pintype "passive"))
      (node (ref "U4") (pin "3") (pinfunction "GND_3") (pintype "passive"))
      (node (ref "U5") (pin "1") (pinfunction "CLKIN_1") (pintype "passive"))
      (node (ref "U5") (pin "11") (pinfunction "FSYNC_11") (pintype "passive"))
      (node (ref "U5") (pin "18") (pinfunction "GND_18") (pintype "passive"))
    )
    (net (code "51") (name "GND_2") (class "Default")
      (node (ref "C22") (pin "1") (pintype "passive"))
      (node (ref "C24") (pin "1") (pintype "passive"))
      (node (ref "C25") (pin "1") (pintype "passive"))
      (node (ref "C26") (pin "1") (pintype "passive"))
      (node (ref "LED1") (pin "2") (pinfunction "K_2") (pintype "passive"))
      (node (ref "P5") (pin "9") (pinfunction "9_9") (pintype "passive"))
      (node (ref "R28") (pin "1") (pintype "passive"))
      (node (ref "U6") (pin "2") (pinfunction "LED-_2") (pintype "passive"))
      (node (ref "U6") (pin "5") (pinfunction "GND_5") (pintype "passive"))
      (node (ref "U7") (pin "11") (pinfunction "11_11") (pintype "passive"))
      (node (ref "U8") (pin "16") (pinfunction "GND_16") (pintype "passive"))
      (node (ref "U9") (pin "4") (pinfunction "VSS_4") (pintype "power_in"))
    )
    (net (code "52") (name "Net-(C20-Pad1)") (class "Default")
      (node (ref "C20") (pin "1") (pintype "passive"))
      (node (ref "R30") (pin "1") (pintype "passive"))
    )
    (net (code "53") (name "Net-(C21-Pad1)") (class "Default")
      (node (ref "C21") (pin "1") (pintype "passive"))
      (node (ref "R29") (pin "1") (pintype "passive"))
      (node (ref "U7") (pin "1") (pintype "passive"))
    )
    (net (code "54") (name "Net-(C23-Pad1)") (class "Default")
      (node (ref "C23") (pin "1") (pintype "passive"))
      (node (ref "R31") (pin "2") (pintype "passive"))
      (node (ref "R32") (pin "1") (pintype "passive"))
      (node (ref "U7") (pin "12") (pinfunction "12_12") (pintype "passive"))
      (node (ref "U7") (pin "15") (pinfunction "15_15") (pintype "passive"))
    )
    (net (code "55") (name "Net-(C23-Pad2)") (class "Default")
      (node (ref "C23") (pin "2") (pintype "passive"))
      (node (ref "R30") (pin "2") (pintype "passive"))
      (node (ref "R31") (pin "1") (pintype "passive"))
      (node (ref "U7") (pin "16") (pinfunction "16_16") (pintype "passive"))
    )
    (net (code "56") (name "Net-(C24-Pad2)") (class "Default")
      (node (ref "C24") (pin "2") (pintype "passive"))
      (node (ref "R33") (pin "2") (pintype "passive"))
      (node (ref "U7") (pin "9") (pinfunction "9_9") (pintype "passive"))
    )
    (net (code "57") (name "Net-(I1-L_A)") (class "Default")
      (node (ref "I1") (pin "22") (pinfunction "L_A_22") (pintype "power_in"))
      (node (ref "Q3") (pin "2") (pinfunction "E_2") (pintype "passive"))
    )
    (net (code "58") (name "Net-(LED1-A)") (class "Default")
      (node (ref "LED1") (pin "1") (pinfunction "A_1") (pintype "passive"))
      (node (ref "R35") (pin "1") (pintype "passive"))
      (node (ref "R_S1") (pin "2") (pintype "passive"))
    )
    (net (code "59") (name "Net-(LS1-Pad2)") (class "Default")
      (node (ref "LS1") (pin "2") (pinfunction "2_2") (pintype "passive"))
      (node (ref "R41") (pin "2") (pintype "passive"))
      (node (ref "R42") (pin "1") (pintype "passive"))
    )
    (net (code "60") (name "Net-(P1-T1_+)") (class "Default")
      (node (ref "P1") (pin "1") (pinfunction "T1_+_1") (pintype "passive"))
      (node (ref "R14") (pin "1") (pintype "passive"))
    )
    (net (code "61") (name "Net-(Q1-C)") (class "Default")
      (node (ref "Q1") (pin "3") (pinfunction "C_3") (pintype "passive"))
      (node (ref "R17") (pin "2") (pintype "passive"))
    )
    (net (code "62") (name "Net-(Q2-E)") (class "Default")
      (node (ref "P4") (pin "1") (pinfunction "1_1") (pintype "passive"))
      (node (ref "Q2") (pin "2") (pinfunction "E_2") (pintype "passive"))
    )
    (net (code "63") (name "Net-(Q3-B)") (class "Default")
      (node (ref "Q3") (pin "1") (pinfunction "B_1") (pintype "passive"))
      (node (ref "R_LA") (pin "2") (pintype "passive"))
    )
    (net (code "64") (name "Net-(R26-Pad2)") (class "Default")
      (node (ref "R26") (pin "2") (pintype "passive"))
      (node (ref "U6") (pin "1") (pinfunction "LED+_1") (pintype "passive"))
    )
    (net (code "65") (name "Net-(R27-Pad2)") (class "Default")
      (node (ref "R27") (pin "2") (pintype "passive"))
      (node (ref "U6") (pin "3") (pinfunction "LED+_3") (pintype "passive"))
    )
    (net (code "66") (name "Net-(R32-Pad2)") (class "Default")
      (node (ref "R32") (pin "2") (pintype "passive"))
      (node (ref "R34") (pin "1") (pintype "passive"))
      (node (ref "U7") (pin "10") (pinfunction "10_10") (pintype "passive"))
    )
    (net (code "67") (name "Net-(R33-Pad1)") (class "Default")
      (node (ref "R33") (pin "1") (pintype "passive"))
      (node (ref "U7") (pin "13") (pinfunction "13_13") (pintype "passive"))
      (node (ref "U7") (pin "14") (pinfunction "14_14") (pintype "passive"))
    )
    (net (code "68") (name "Net-(R34-Pad2)") (class "Default")
      (node (ref "R34") (pin "2") (pintype "passive"))
      (node (ref "U7") (pin "3") (pintype "passive"))
      (node (ref "U7") (pin "8") (pintype "passive"))
    )
    (net (code "69") (name "Net-(R35-Pad2)") (class "Default")
      (node (ref "R35") (pin "2") (pintype "passive"))
      (node (ref "R_S2") (pin "2") (pintype "passive"))
      (node (ref "U7") (pin "4") (pintype "passive"))
      (node (ref "U7") (pin "5") (pintype "passive"))
    )
    (net (code "70") (name "Net-(U1-BOOT0)") (class "Default")
      (node (ref "R4") (pin "2") (pintype "passive"))
      (node (ref "U1") (pin "60") (pinfunction "BOOT0_60") (pintype "passive"))
    )
    (net (code "71") (name "Net-(U1-PB2{slash}BOOT1)") (class "Default")
      (node (ref "R5") (pin "2") (pintype "passive"))
      (node (ref "U1") (pin "28") (pinfunction "PB2/BOOT1_28") (pintype "passive"))
    )
    (net (code "72") (name "Net-(U1-PC14{slash}OSC32_IN)") (class "Default")
      (node (ref "C4") (pin "1") (pintype "passive"))
      (node (ref "U1") (pin "3") (pinfunction "PC14/OSC32_IN_3") (pintype "passive"))
      (node (ref "Y2") (pin "2") (pinfunction "OSC2_2") (pintype "power_in"))
    )
    (net (code "73") (name "Net-(U1-PC15{slash}OSC32_OUT)") (class "Default")
      (node (ref "C3") (pin "1") (pintype "passive"))
      (node (ref "U1") (pin "4") (pinfunction "PC15/OSC32_OUT_4") (pintype "passive"))
      (node (ref "Y2") (pin "1") (pinfunction "OSC1_1") (pintype "passive"))
    )
    (net (code "74") (name "Net-(U1-PH0{slash}OSC_IN)") (class "Default")
      (node (ref "C1") (pin "2") (pintype "passive"))
      (node (ref "R1") (pin "1") (pintype "passive"))
      (node (ref "U1") (pin "5") (pinfunction "PH0/OSC_IN_5") (pintype "passive"))
      (node (ref "Y1") (pin "1") (pinfunction "OSC1_1") (pintype "passive"))
    )
    (net (code "75") (name "Net-(U1-PH1{slash}OSC_OUT)") (class "Default")
      (node (ref "C2") (pin "2") (pintype "passive"))
      (node (ref "R1") (pin "2") (pintype "passive"))
      (node (ref "U1") (pin "6") (pinfunction "PH1/OSC_OUT_6") (pintype "passive"))
      (node (ref "Y1") (pin "2") (pinfunction "OSC2_2") (pintype "power_in"))
    )
    (net (code "76") (name "Net-(U1-VCAP_1)") (class "Default")
      (node (ref "C7") (pin "1") (pintype "passive"))
      (node (ref "U1") (pin "31") (pinfunction "VCAP_1_31") (pintype "passive"))
    )
    (net (code "77") (name "Net-(U1-VCAP_2)") (class "Default")
      (node (ref "C8") (pin "1") (pintype "passive"))
      (node (ref "U1") (pin "47") (pinfunction "VCAP_2_47") (pintype "passive"))
    )
    (net (code "78") (name "Net-(U1-VDDA)") (class "Default")
      (node (ref "C5") (pin "1") (pintype "passive"))
      (node (ref "C6") (pin "1") (pintype "passive"))
      (node (ref "R2") (pin "2") (pintype "passive"))
      (node (ref "U1") (pin "13") (pinfunction "VDDA_13") (pintype "passive"))
    )
    (net (code "79") (name "Net-(U2-ADJ{slash}BYP)") (class "Default")
      (node (ref "R10") (pin "2") (pintype "passive"))
      (node (ref "R9") (pin "1") (pintype "passive"))
      (node (ref "U2") (pin "4") (pinfunction "ADJ/BYP_4") (pintype "passive"))
    )
    (net (code "80") (name "Net-(U2-EN)") (class "Default")
      (node (ref "R8") (pin "1") (pintype "passive"))
      (node (ref "U2") (pin "3") (pinfunction "EN_3") (pintype "passive"))
    )
    (net (code "81") (name "Net-(U3-ADJ{slash}BYP)") (class "Default")
      (node (ref "R12") (pin "1") (pintype "passive"))
      (node (ref "R13") (pin "2") (pintype "passive"))
      (node (ref "U3") (pin "4") (pinfunction "ADJ/BYP_4") (pintype "passive"))
    )
    (net (code "82") (name "Net-(U3-EN)") (class "Default")
      (node (ref "R11") (pin "1") (pintype "passive"))
      (node (ref "U3") (pin "3") (pinfunction "EN_3") (pintype "passive"))
    )
    (net (code "83") (name "Net-(U4-CE)") (class "Default")
      (node (ref "C15") (pin "1") (pintype "passive"))
      (node (ref "R14") (pin "2") (pintype "passive"))
      (node (ref "U4") (pin "4") (pinfunction "VCC_4") (pintype "passive"))
      (node (ref "U4") (pin "8") (pinfunction "CE_8") (pintype "passive"))
    )
    (net (code "84") (name "Net-(U4-PR)") (class "Default")
      (node (ref "R15") (pin "1") (pintype "passive"))
      (node (ref "U4") (pin "2") (pinfunction "PR_2") (pintype "passive"))
    )
    (net (code "85") (name "Net-(U5-AD0)") (class "Default")
      (node (ref "R25") (pin "2") (pintype "passive"))
      (node (ref "U5") (pin "9") (pinfunction "AD0_9") (pintype "passive"))
    )
    (net (code "86") (name "Net-(U5-CPOUT)") (class "Default")
      (node (ref "C18") (pin "2") (pintype "passive"))
      (node (ref "U5") (pin "20") (pinfunction "CPOUT_20") (pintype "passive"))
    )
    (net (code "87") (name "Net-(U5-INT)") (class "Default")
      (node (ref "R24") (pin "2") (pintype "passive"))
      (node (ref "U5") (pin "12") (pinfunction "INT_12") (pintype "passive"))
    )
    (net (code "88") (name "Net-(U5-REGOUT)") (class "Default")
      (node (ref "C17") (pin "2") (pintype "passive"))
      (node (ref "U5") (pin "10") (pinfunction "REGOUT_10") (pintype "passive"))
    )
    (net (code "89") (name "Net-(U5-SCL)") (class "Default")
      (node (ref "R22") (pin "2") (pintype "passive"))
      (node (ref "U5") (pin "23") (pinfunction "SCL_23") (pintype "passive"))
    )
    (net (code "90") (name "Net-(U5-SDA)") (class "Default")
      (node (ref "R23") (pin "2") (pintype "passive"))
      (node (ref "U5") (pin "24") (pinfunction "SDA_24") (pintype "passive"))
    )
    (net (code "91") (name "Net-(U6-VOUT)") (class "Default")
      (node (ref "C20") (pin "2") (pintype "passive"))
      (node (ref "R28") (pin "2") (pintype "passive"))
      (node (ref "R29") (pin "2") (pintype "passive"))
      (node (ref "U6") (pin "6") (pinfunction "VOUT_6") (pintype "passive"))
    )
    (net (code "92") (name "Net-(U8-WPS)") (class "Default")
      (node (ref "R36") (pin "1") (pintype "passive"))
      (node (ref "U8") (pin "14") (pinfunction "WPS_14") (pintype "passive"))
    )
    (net (code "93") (name "Net-(U8-nReload)") (class "Default")
      (node (ref "R37") (pin "1") (pintype "passive"))
      (node (ref "U8") (pin "12") (pinfunction "nReload_12") (pintype "passive"))
    )
    (net (code "94") (name "VCC3.3") (class "Default")
      (node (ref "C11") (pin "1") (pintype "passive"))
      (node (ref "C12") (pin "2") (pinfunction "GND_2") (pintype "passive"))
      (node (ref "C19") (pin "2") (pintype "passive"))
      (node (ref "I1") (pin "18") (pinfunction "IOVCC_18") (pintype "power_in"))
      (node (ref "I1") (pin "20") (pinfunction "VCI_20") (pintype "power_in"))
      (node (ref "I2") (pin "1") (pinfunction "VDD_1") (pintype "power_in"))
      (node (ref "P3") (pin "1") (pinfunction "1_1") (pintype "passive"))
      (node (ref "P6") (pin "1") (pinfunction "1_1") (pintype "passive"))
      (node (ref "Q2") (pin "3") (pinfunction "C_3") (pintype "passive"))
      (node (ref "Q3") (pin "3") (pinfunction "C_3") (pintype "passive"))
      (node (ref "R18") (pin "2") (pintype "passive"))
      (node (ref "R19") (pin "1") (pintype "passive"))
      (node (ref "R20") (pin "1") (pintype "passive"))
      (node (ref "R21") (pin "1") (pintype "passive"))
      (node (ref "R3") (pin "1") (pintype "passive"))
      (node (ref "R41") (pin "1") (pintype "passive"))
      (node (ref "R6") (pin "2") (pintype "passive"))
      (node (ref "R7") (pin "2") (pintype "passive"))
      (node (ref "R9") (pin "2") (pintype "passive"))
      (node (ref "U1") (pin "19") (pinfunction "VDD_1_19") (pintype "passive"))
      (node (ref "U1") (pin "32") (pinfunction "VDD_2_32") (pintype "passive"))
      (node (ref "U1") (pin "48") (pinfunction "VDD_3_48") (pintype "passive"))
      (node (ref "U1") (pin "64") (pinfunction "VDD_4_64") (pintype "passive"))
      (node (ref "U2") (pin "5") (pinfunction "VOUT_5") (pintype "passive"))
      (node (ref "U5") (pin "13") (pinfunction "VDD_13") (pintype "passive"))
      (node (ref "U5") (pin "8") (pinfunction "VLOGIC_8") (pintype "passive"))
    )
    (net (code "95") (name "VCC3.3A") (class "Default")
      (node (ref "R2") (pin "1") (pintype "passive"))
      (node (ref "R6") (pin "1") (pintype "passive"))
      (node (ref "R7") (pin "1") (pintype "passive"))
    )
    (net (code "96") (name "VCC3.3_2") (class "Default")
      (node (ref "C21") (pin "2") (pintype "passive"))
      (node (ref "C22") (pin "2") (pintype "passive"))
      (node (ref "C25") (pin "2") (pintype "passive"))
      (node (ref "C26") (pin "2") (pintype "passive"))
      (node (ref "P5") (pin "10") (pinfunction "10_10") (pintype "passive"))
      (node (ref "R26") (pin "1") (pintype "passive"))
      (node (ref "R27") (pin "1") (pintype "passive"))
      (node (ref "R36") (pin "2") (pintype "passive"))
      (node (ref "R37") (pin "2") (pintype "passive"))
      (node (ref "R38") (pin "2") (pintype "passive"))
      (node (ref "U6") (pin "4") (pinfunction "VCC_4") (pintype "passive"))
      (node (ref "U7") (pin "2") (pintype "passive"))
      (node (ref "U8") (pin "15") (pinfunction "DVDD_15") (pintype "passive"))
      (node (ref "U9") (pin "2") (pinfunction "VDD_2") (pintype "power_in"))
    )
    (net (code "97") (name "VCC4.2") (class "Default")
      (node (ref "C10") (pin "1") (pintype "passive"))
      (node (ref "C13") (pin "1") (pinfunction "VCC_1") (pintype "passive"))
      (node (ref "C16") (pin "2") (pintype "passive"))
      (node (ref "C9") (pin "1") (pinfunction "VCC_1") (pintype "passive"))
      (node (ref "KEY1") (pin "1") (pinfunction "P1_1") (pintype "passive"))
      (node (ref "P2") (pin "1") (pinfunction "VCC_1") (pintype "passive"))
      (node (ref "R11") (pin "2") (pintype "passive"))
      (node (ref "R17") (pin "1") (pintype "passive"))
      (node (ref "R40") (pin "2") (pintype "passive"))
      (node (ref "U2") (pin "1") (pinfunction "VIN_1") (pintype "passive"))
      (node (ref "U3") (pin "1") (pinfunction "VIN_1") (pintype "passive"))
      (node (ref "U4") (pin "5") (pinfunction "BAT_5") (pintype "passive"))
    )
    (net (code "98") (name "unconnected-(I1-D8-Pad4)") (class "Default")
      (node (ref "I1") (pin "4") (pinfunction "D8_4") (pintype "power_in+no_connect"))
    )
    (net (code "99") (name "unconnected-(I1-FRK-Pad19)") (class "Default")
      (node (ref "I1") (pin "19") (pinfunction "FRK_19") (pintype "power_in+no_connect"))
    )
    (net (code "100") (name "unconnected-(I2-SPK+-Pad8)") (class "Default")
      (node (ref "I2") (pin "8") (pinfunction "SPK+_8") (pintype "power_in+no_connect"))
    )
    (net (code "101") (name "unconnected-(I2-SPK--Pad9)") (class "Default")
      (node (ref "I2") (pin "9") (pinfunction "SPK-_9") (pintype "power_in+no_connect"))
    )
    (net (code "102") (name "unconnected-(P2-TEMP-Pad3)") (class "Default")
      (node (ref "P2") (pin "3") (pinfunction "TEMP_3") (pintype "passive+no_connect"))
    )
    (net (code "103") (name "unconnected-(Q2-B-Pad1)") (class "Default")
      (node (ref "Q2") (pin "1") (pinfunction "B_1") (pintype "passive"))
    )
    (net (code "104") (name "unconnected-(R_M-Pad2)") (class "Default")
      (node (ref "R_M") (pin "2") (pintype "passive"))
    )
    (net (code "105") (name "unconnected-(U1-PA15{slash}JTDI{slash}SPI3_NSS{slash}I2S3_WS{slash}TIM2_CH1_ETR{slash}SPI1_NSS-Pad50)") (class "Default")
      (node (ref "U1") (pin "50") (pinfunction "PA15/JTDI/SPI3_NSS/I2S3_WS/TIM2_CH1_ETR/SPI1_NSS_50") (pintype "passive"))
    )
    (net (code "106") (name "unconnected-(U1-PB5{slash}I2C1_SMBA{slash}CAN2_RX{slash}OTG_HS_ULPI_D7{slash}ETH_PPS_OUT{slash}TIM3_CH2{slash}SPI1_MOSI{slash}SPI3_MOSI{slash}DCMI_D10{slash}I2S3_SD-Pad57)") (class "Default")
      (node (ref "U1") (pin "57") (pinfunction "PB5/I2C1_SMBA/CAN2_RX/OTG_HS_ULPI_D7/ETH_PPS_OUT/TIM3_CH2/SPI1_MOSI/SPI3_MOSI/DCMI_D10/I2S3_SD_57") (pintype "passive"))
    )
    (net (code "107") (name "unconnected-(U1-PB6{slash}I2C1_SCL{slash}TIM4_CH1{slash}CAN2_TX{slash}DCMI_D5{slash}USART1_TX-Pad58)") (class "Default")
      (node (ref "U1") (pin "58") (pinfunction "PB6/I2C1_SCL/TIM4_CH1/CAN2_TX/DCMI_D5/USART1_TX_58") (pintype "passive"))
    )
    (net (code "108") (name "unconnected-(U1-PB10{slash}SPI2_SCK{slash}I2S2_CK{slash}I2C2_SCL{slash}U3_TX{slash}OTG_HS_ULPI_D3{slash}ETH_MII_RX_ER{slash}TIM2_CH3-Pad29)") (class "Default")
      (node (ref "U1") (pin "29") (pinfunction "PB10/SPI2_SCK/I2S2_CK/I2C2_SCL/U3_TX/OTG_HS_ULPI_D3/ETH_MII_RX_ER/TIM2_CH3_29") (pintype "passive"))
    )
    (net (code "109") (name "unconnected-(U1-PB11{slash}I2C2_SDA{slash}UT3_RX{slash}OTG_HS_ULPI_D4{slash}ETH_RMII_TX_EN{slash}ETH_MII_TX_EN{slash}TIM2_CH4-Pad30)") (class "Default")
      (node (ref "U1") (pin "30") (pinfunction "PB11/I2C2_SDA/UT3_RX/OTG_HS_ULPI_D4/ETH_RMII_TX_EN/ETH_MII_TX_EN/TIM2_CH4_30") (pintype "passive"))
    )
    (net (code "110") (name "unconnected-(U1-PC9{slash}I2S_CKIN{slash}MCO2{slash}TIM8_CH4{slash}SDIO_D1{slash}I2C3_SDA{slash}DCMI_D3{slash}TIM3_CH4-Pad40)") (class "Default")
      (node (ref "U1") (pin "40") (pinfunction "PC9/I2S_CKIN/MCO2/TIM8_CH4/SDIO_D1/I2C3_SDA/DCMI_D3/TIM3_CH4_40") (pintype "passive"))
    )
    (net (code "111") (name "unconnected-(U1-PC10{slash}SPI3_SCK{slash}I2S3_CK{slash}U4_TX{slash}SDIO_D2{slash}DCMI_D8{slash}U3_TX-Pad51)") (class "Default")
      (node (ref "U1") (pin "51") (pinfunction "PC10/SPI3_SCK/I2S3_CK/U4_TX/SDIO_D2/DCMI_D8/U3_TX_51") (pintype "passive"))
    )
    (net (code "112") (name "unconnected-(U1-PC13{slash}RTC_OUT{slash}RTC_TAMP1{slash}RTC_TS-Pad2)") (class "Default")
      (node (ref "U1") (pin "2") (pinfunction "PC13/RTC_OUT/RTC_TAMP1/RTC_TS_2") (pintype "passive"))
    )
    (net (code "113") (name "unconnected-(U1-PD2{slash}TIM3_ETR{slash}U5_RX{slash}SDIO_CMD{slash}DCMI_D11-Pad54)") (class "Default")
      (node (ref "U1") (pin "54") (pinfunction "PD2/TIM3_ETR/U5_RX/SDIO_CMD/DCMI_D11_54") (pintype "passive"))
    )
    (net (code "114") (name "unconnected-(U5-AUX_CL-Pad7)") (class "Default")
      (node (ref "U5") (pin "7") (pinfunction "AUX_CL_7") (pintype "passive+no_connect"))
    )
    (net (code "115") (name "unconnected-(U5-AUX_DA-Pad6)") (class "Default")
      (node (ref "U5") (pin "6") (pinfunction "AUX_DA_6") (pintype "passive+no_connect"))
    )
    (net (code "116") (name "unconnected-(U5-NC-Pad2)") (class "Default")
      (node (ref "U5") (pin "2") (pinfunction "NC_2") (pintype "passive+no_connect"))
    )
    (net (code "117") (name "unconnected-(U5-NC-Pad3)") (class "Default")
      (node (ref "U5") (pin "3") (pinfunction "NC_3") (pintype "passive+no_connect"))
    )
    (net (code "118") (name "unconnected-(U5-NC-Pad4)") (class "Default")
      (node (ref "U5") (pin "4") (pinfunction "NC_4") (pintype "passive+no_connect"))
    )
    (net (code "119") (name "unconnected-(U5-NC-Pad5)") (class "Default")
      (node (ref "U5") (pin "5") (pinfunction "NC_5") (pintype "passive+no_connect"))
    )
    (net (code "120") (name "unconnected-(U5-NC-Pad14)") (class "Default")
      (node (ref "U5") (pin "14") (pinfunction "NC_14") (pintype "passive+no_connect"))
    )
    (net (code "121") (name "unconnected-(U5-NC-Pad15)") (class "Default")
      (node (ref "U5") (pin "15") (pinfunction "NC_15") (pintype "passive+no_connect"))
    )
    (net (code "122") (name "unconnected-(U5-NC-Pad16)") (class "Default")
      (node (ref "U5") (pin "16") (pinfunction "NC_16") (pintype "passive+no_connect"))
    )
    (net (code "123") (name "unconnected-(U5-NC-Pad17)") (class "Default")
      (node (ref "U5") (pin "17") (pinfunction "NC_17") (pintype "passive+no_connect"))
    )
    (net (code "124") (name "unconnected-(U5-RESV-Pad19)") (class "Default")
      (node (ref "U5") (pin "19") (pinfunction "RESV_19") (pintype "passive+no_connect"))
    )
    (net (code "125") (name "unconnected-(U5-RESV-Pad21)") (class "Default")
      (node (ref "U5") (pin "21") (pinfunction "RESV_21") (pintype "passive+no_connect"))
    )
    (net (code "126") (name "unconnected-(U5-RESV-Pad22)") (class "Default")
      (node (ref "U5") (pin "22") (pinfunction "RESV_22") (pintype "passive+no_connect"))
    )
    (net (code "127") (name "unconnected-(U7-Pad6)") (class "Default")
      (node (ref "U7") (pin "6") (pintype "passive+no_connect"))
    )
    (net (code "128") (name "unconnected-(U7-Pad7)") (class "Default")
      (node (ref "U7") (pin "7") (pintype "passive+no_connect"))
    )
    (net (code "129") (name "unconnected-(U8-ANT-2.4G-Pad17)") (class "Default")
      (node (ref "U8") (pin "17") (pinfunction "ANT-2.4G_17") (pintype "passive+no_connect"))
    )
    (net (code "130") (name "unconnected-(U8-GPIO9-Pad9)") (class "Default")
      (node (ref "U8") (pin "9") (pinfunction "GPIO9_9") (pintype "passive+no_connect"))
    )
    (net (code "131") (name "unconnected-(U8-NC-Pad1)") (class "Default")
      (node (ref "U8") (pin "1") (pinfunction "NC_1") (pintype "passive+no_connect"))
    )
    (net (code "132") (name "unconnected-(U8-NC-Pad2)") (class "Default")
      (node (ref "U8") (pin "2") (pinfunction "NC_2") (pintype "passive+no_connect"))
    )
    (net (code "133") (name "unconnected-(U8-NC-Pad3)") (class "Default")
      (node (ref "U8") (pin "3") (pinfunction "NC_3") (pintype "passive+no_connect"))
    )
    (net (code "134") (name "unconnected-(U8-NC-Pad4)") (class "Default")
      (node (ref "U8") (pin "4") (pinfunction "NC_4") (pintype "passive+no_connect"))
    )
    (net (code "135") (name "unconnected-(U8-UART0-CTS-Pad7)") (class "Default")
      (node (ref "U8") (pin "7") (pinfunction "UART0-CTS_7") (pintype "passive+no_connect"))
    )
    (net (code "136") (name "unconnected-(U8-UART0-RTS-Pad8)") (class "Default")
      (node (ref "U8") (pin "8") (pinfunction "UART0-RTS_8") (pintype "passive+no_connect"))
    )
  )
)
